# 1-Schematic_Smart_dual_relay_board.net
KiCad netlist of a schematic drawn in EasyEDA
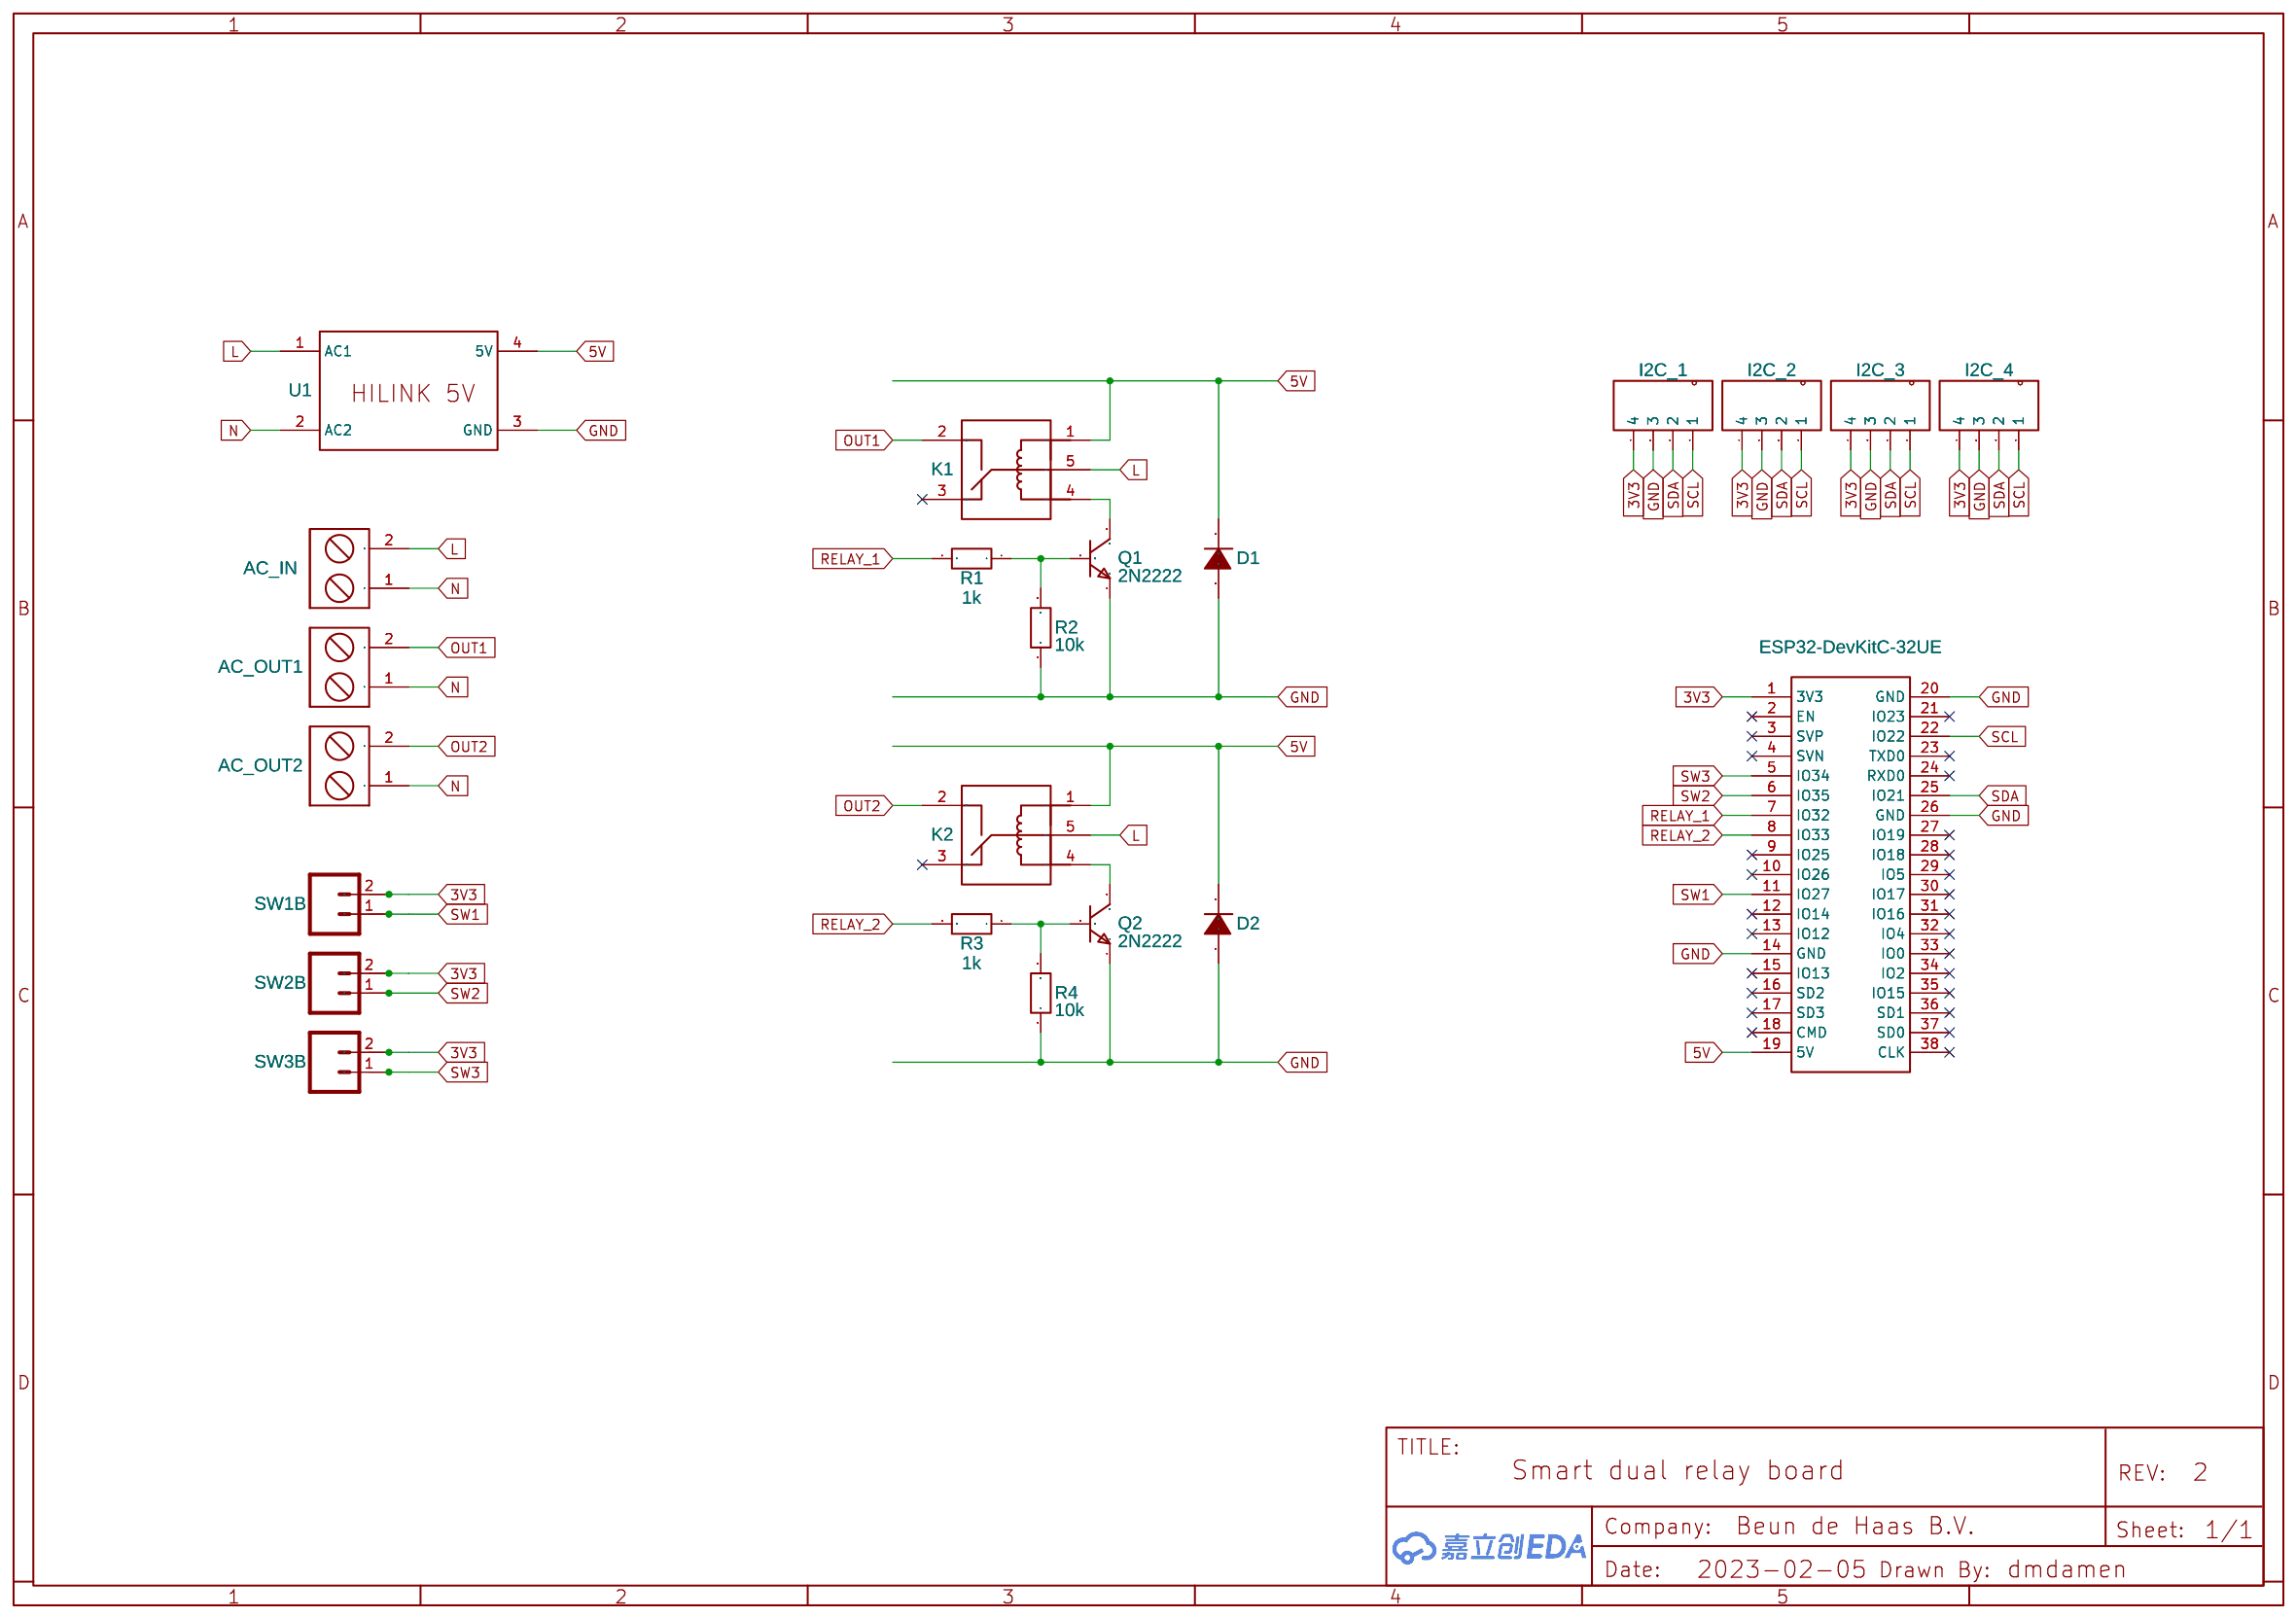
[diagram p0: schematic sheet]

(export (version "E")
  (design (tool "Eeschema 10.0.6"))
  (components
    (comp (ref "AC_IN")
      (value "10MM SCREW TERMINAL 2P")
      (libsource (lib "") (part "7.62MM PITCH 2 PIN BARRIER SCREW TERMINAL BLOCK CONNECTOR 300V 20A"))
    )
    (comp (ref "AC_OUT1")
      (value "10MM SCREW TERMINAL 2P")
      (libsource (lib "") (part "7.62MM PITCH 2 PIN BARRIER SCREW TERMINAL BLOCK CONNECTOR 300V 20A_1"))
    )
    (comp (ref "AC_OUT2")
      (value "10MM SCREW TERMINAL 2P")
      (libsource (lib "") (part "7.62MM PITCH 2 PIN BARRIER SCREW TERMINAL BLOCK CONNECTOR 300V 20A_1"))
    )
    (comp (ref "D1")
      (value "1N4001_C478800")
      (fields (field (name "BOM_Manufacturer Part") "1N4001") (field (name "BOM_Supplier Part") "C478800"))
      (libsource (lib "") (part "1N4001_C478800"))
    )
    (comp (ref "D2")
      (value "1N4001_C478800")
      (fields (field (name "BOM_Manufacturer Part") "1N4001") (field (name "BOM_Supplier Part") "C478800"))
      (libsource (lib "") (part "1N4001_C478800"))
    )
    (comp (ref "I2C_1") (value "I2C 1") (libsource (lib "") (part "PINHEADER-4PIN")))
    (comp (ref "I2C_2") (value "I2C 2") (libsource (lib "") (part "PINHEADER-4PIN")))
    (comp (ref "I2C_3") (value "I2C 3") (libsource (lib "") (part "PINHEADER-4PIN")))
    (comp (ref "I2C_4") (value "I2C 3") (libsource (lib "") (part "PINHEADER-4PIN")))
    (comp (ref "K1")
      (value "SRD-03VDC-SL-C_C496430")
      (fields
        (field (name "BOM_Manufacturer Part") "SRD-03VDC-SL-C")
        (field (name "BOM_Supplier Part") "C496430")
      )
      (libsource (lib "") (part "SRD-03VDC-SL-C_C496430"))
    )
    (comp (ref "K2")
      (value "SRD-03VDC-SL-C_C496430")
      (fields
        (field (name "BOM_Manufacturer Part") "SRD-03VDC-SL-C")
        (field (name "BOM_Supplier Part") "C496430")
      )
      (libsource (lib "") (part "SRD-03VDC-SL-C_C496430"))
    )
    (comp (ref "Q1")
      (value "2N2222")
      (fields (field (name "BOM_Manufacturer Part") "2N2222A") (field (name "BOM_Supplier Part") "C118536"))
      (libsource (lib "") (part "2N2222"))
    )
    (comp (ref "Q2")
      (value "2N2222")
      (fields (field (name "BOM_Manufacturer Part") "2N2222A") (field (name "BOM_Supplier Part") "C118536"))
      (libsource (lib "") (part "2N2222"))
    )
    (comp (ref "R1") (value "1k") (libsource (lib "") (part "R_0603_EU_1")))
    (comp (ref "R2") (value "10k") (libsource (lib "") (part "R_0603_EU")))
    (comp (ref "R3") (value "1k") (libsource (lib "") (part "R_0603_EU_1")))
    (comp (ref "R4") (value "10k") (libsource (lib "") (part "R_0603_EU")))
    (comp (ref "SW1B") (value "M02") (libsource (lib "") (part "M02")))
    (comp (ref "SW2B") (value "M02") (libsource (lib "") (part "M02_1")))
    (comp (ref "SW3B") (value "M02") (libsource (lib "") (part "M02_2")))
    (comp (ref "U1")
      (value "HILINK 5V corrected")
      (fields (field (name "BOM_Manufacturer Part") "HILINK 5V"))
      (libsource (lib "") (part "HILINK 5V corrected"))
    )
    (comp (ref "U2")
      (value "ESP32-DevKitC-32UE")
      (fields (field (name "BOM_Manufacturer Part") "ESP32 DEVKIT V.4"))
      (libsource (lib "") (part "ESP32-DevKitC-32UE"))
    )
  )
  (nets
    (net (code "1") (name "3V3") (class "Default")
      (node (ref "I2C_1") (pin "4") (pinfunction "4_4") (pintype "input"))
      (node (ref "I2C_2") (pin "4") (pinfunction "4_4") (pintype "input"))
      (node (ref "I2C_3") (pin "4") (pinfunction "4_4") (pintype "input"))
      (node (ref "I2C_4") (pin "4") (pinfunction "4_4") (pintype "input"))
      (node (ref "SW1B") (pin "2") (pinfunction "2_2") (pintype "unspecified"))
      (node (ref "SW2B") (pin "2") (pinfunction "2_2") (pintype "unspecified"))
      (node (ref "SW3B") (pin "2") (pinfunction "2_2") (pintype "unspecified"))
      (node (ref "U2") (pin "1") (pinfunction "3V3_1") (pintype "unspecified"))
    )
    (net (code "2") (name "5V") (class "Default")
      (node (ref "D1") (pin "1") (pinfunction "K_1") (pintype "unspecified"))
      (node (ref "D2") (pin "1") (pinfunction "K_1") (pintype "unspecified"))
      (node (ref "K1") (pin "1") (pinfunction "1_1") (pintype "unspecified"))
      (node (ref "K2") (pin "1") (pinfunction "1_1") (pintype "unspecified"))
      (node (ref "U1") (pin "4") (pinfunction "5V_4") (pintype "unspecified"))
      (node (ref "U2") (pin "19") (pinfunction "5V_19") (pintype "unspecified"))
    )
    (net (code "3") (name "GND") (class "Default")
      (node (ref "D1") (pin "2") (pinfunction "A_2") (pintype "unspecified"))
      (node (ref "D2") (pin "2") (pinfunction "A_2") (pintype "unspecified"))
      (node (ref "I2C_1") (pin "3") (pinfunction "3_3") (pintype "input"))
      (node (ref "I2C_2") (pin "3") (pinfunction "3_3") (pintype "input"))
      (node (ref "I2C_3") (pin "3") (pinfunction "3_3") (pintype "input"))
      (node (ref "I2C_4") (pin "3") (pinfunction "3_3") (pintype "input"))
      (node (ref "Q1") (pin "1") (pinfunction "E_1") (pintype "unspecified"))
      (node (ref "Q2") (pin "1") (pinfunction "E_1") (pintype "unspecified"))
      (node (ref "R2") (pin "1") (pinfunction "1_1") (pintype "unspecified"))
      (node (ref "R4") (pin "1") (pinfunction "1_1") (pintype "unspecified"))
      (node (ref "U1") (pin "3") (pinfunction "GND_3") (pintype "unspecified"))
      (node (ref "U2") (pin "14") (pinfunction "GND_14") (pintype "unspecified"))
      (node (ref "U2") (pin "20") (pinfunction "GND_20") (pintype "unspecified"))
      (node (ref "U2") (pin "26") (pinfunction "GND_26") (pintype "unspecified"))
    )
    (net (code "4") (name "L") (class "Default")
      (node (ref "AC_IN") (pin "2") (pinfunction "2_2") (pintype "unspecified"))
      (node (ref "K1") (pin "5") (pinfunction "5_5") (pintype "unspecified"))
      (node (ref "K2") (pin "5") (pinfunction "5_5") (pintype "unspecified"))
      (node (ref "U1") (pin "1") (pinfunction "AC1_1") (pintype "unspecified"))
    )
    (net (code "5") (name "N") (class "Default")
      (node (ref "AC_IN") (pin "1") (pinfunction "1_1") (pintype "unspecified"))
      (node (ref "AC_OUT1") (pin "1") (pinfunction "1_1") (pintype "unspecified"))
      (node (ref "AC_OUT2") (pin "1") (pinfunction "1_1") (pintype "unspecified"))
      (node (ref "U1") (pin "2") (pinfunction "AC2_2") (pintype "unspecified"))
    )
    (net (code "6") (name "Net-(Q1-B)") (class "Default")
      (node (ref "Q1") (pin "2") (pinfunction "B_2") (pintype "unspecified"))
      (node (ref "R1") (pin "1") (pinfunction "1_1") (pintype "unspecified"))
      (node (ref "R2") (pin "2") (pinfunction "2_2") (pintype "unspecified"))
    )
    (net (code "7") (name "Net-(Q1-C)") (class "Default")
      (node (ref "K1") (pin "4") (pinfunction "4_4") (pintype "unspecified"))
      (node (ref "Q1") (pin "3") (pinfunction "C_3") (pintype "unspecified"))
    )
    (net (code "8") (name "Net-(Q2-B)") (class "Default")
      (node (ref "Q2") (pin "2") (pinfunction "B_2") (pintype "unspecified"))
      (node (ref "R3") (pin "1") (pinfunction "1_1") (pintype "unspecified"))
      (node (ref "R4") (pin "2") (pinfunction "2_2") (pintype "unspecified"))
    )
    (net (code "9") (name "Net-(Q2-C)") (class "Default")
      (node (ref "K2") (pin "4") (pinfunction "4_4") (pintype "unspecified"))
      (node (ref "Q2") (pin "3") (pinfunction "C_3") (pintype "unspecified"))
    )
    (net (code "10") (name "OUT1") (class "Default")
      (node (ref "AC_OUT1") (pin "2") (pinfunction "2_2") (pintype "unspecified"))
      (node (ref "K1") (pin "2") (pinfunction "2_2") (pintype "unspecified"))
    )
    (net (code "11") (name "OUT2") (class "Default")
      (node (ref "AC_OUT2") (pin "2") (pinfunction "2_2") (pintype "unspecified"))
      (node (ref "K2") (pin "2") (pinfunction "2_2") (pintype "unspecified"))
    )
    (net (code "12") (name "RELAY_1") (class "Default")
      (node (ref "R1") (pin "2") (pinfunction "2_2") (pintype "unspecified"))
      (node (ref "U2") (pin "7") (pinfunction "IO32_7") (pintype "unspecified"))
    )
    (net (code "13") (name "RELAY_2") (class "Default")
      (node (ref "R3") (pin "2") (pinfunction "2_2") (pintype "unspecified"))
      (node (ref "U2") (pin "8") (pinfunction "IO33_8") (pintype "unspecified"))
    )
    (net (code "14") (name "SCL") (class "Default")
      (node (ref "I2C_1") (pin "1") (pinfunction "1_1") (pintype "input"))
      (node (ref "I2C_2") (pin "1") (pinfunction "1_1") (pintype "input"))
      (node (ref "I2C_3") (pin "1") (pinfunction "1_1") (pintype "input"))
      (node (ref "I2C_4") (pin "1") (pinfunction "1_1") (pintype "input"))
      (node (ref "U2") (pin "22") (pinfunction "IO22_22") (pintype "unspecified"))
    )
    (net (code "15") (name "SDA") (class "Default")
      (node (ref "I2C_1") (pin "2") (pinfunction "2_2") (pintype "input"))
      (node (ref "I2C_2") (pin "2") (pinfunction "2_2") (pintype "input"))
      (node (ref "I2C_3") (pin "2") (pinfunction "2_2") (pintype "input"))
      (node (ref "I2C_4") (pin "2") (pinfunction "2_2") (pintype "input"))
      (node (ref "U2") (pin "25") (pinfunction "IO21_25") (pintype "unspecified"))
    )
    (net (code "16") (name "SW1") (class "Default")
      (node (ref "SW1B") (pin "1") (pinfunction "1_1") (pintype "unspecified"))
      (node (ref "U2") (pin "11") (pinfunction "IO27_11") (pintype "unspecified"))
    )
    (net (code "17") (name "SW2") (class "Default")
      (node (ref "SW2B") (pin "1") (pinfunction "1_1") (pintype "unspecified"))
      (node (ref "U2") (pin "6") (pinfunction "IO35_6") (pintype "unspecified"))
    )
    (net (code "18") (name "SW3") (class "Default")
      (node (ref "SW3B") (pin "1") (pinfunction "1_1") (pintype "unspecified"))
      (node (ref "U2") (pin "5") (pinfunction "IO34_5") (pintype "unspecified"))
    )
    (net (code "19") (name "unconnected-(K1-Pad3)") (class "Default")
      (node (ref "K1") (pin "3") (pinfunction "3_3") (pintype "unspecified+no_connect"))
    )
    (net (code "20") (name "unconnected-(K2-Pad3)") (class "Default")
      (node (ref "K2") (pin "3") (pinfunction "3_3") (pintype "unspecified+no_connect"))
    )
    (net (code "21") (name "unconnected-(U2-CLK-Pad38)") (class "Default")
      (node (ref "U2") (pin "38") (pinfunction "CLK_38") (pintype "unspecified+no_connect"))
    )
    (net (code "22") (name "unconnected-(U2-CMD-Pad18)") (class "Default")
      (node (ref "U2") (pin "18") (pinfunction "CMD_18") (pintype "unspecified+no_connect"))
    )
    (net (code "23") (name "unconnected-(U2-EN-Pad2)") (class "Default")
      (node (ref "U2") (pin "2") (pinfunction "EN_2") (pintype "unspecified+no_connect"))
    )
    (net (code "24") (name "unconnected-(U2-IO0-Pad33)") (class "Default")
      (node (ref "U2") (pin "33") (pinfunction "IO0_33") (pintype "unspecified+no_connect"))
    )
    (net (code "25") (name "unconnected-(U2-IO2-Pad34)") (class "Default")
      (node (ref "U2") (pin "34") (pinfunction "IO2_34") (pintype "unspecified+no_connect"))
    )
    (net (code "26") (name "unconnected-(U2-IO4-Pad32)") (class "Default")
      (node (ref "U2") (pin "32") (pinfunction "IO4_32") (pintype "unspecified+no_connect"))
    )
    (net (code "27") (name "unconnected-(U2-IO5-Pad29)") (class "Default")
      (node (ref "U2") (pin "29") (pinfunction "IO5_29") (pintype "unspecified+no_connect"))
    )
    (net (code "28") (name "unconnected-(U2-IO12-Pad13)") (class "Default")
      (node (ref "U2") (pin "13") (pinfunction "IO12_13") (pintype "unspecified+no_connect"))
    )
    (net (code "29") (name "unconnected-(U2-IO13-Pad15)") (class "Default")
      (node (ref "U2") (pin "15") (pinfunction "IO13_15") (pintype "unspecified+no_connect"))
    )
    (net (code "30") (name "unconnected-(U2-IO14-Pad12)") (class "Default")
      (node (ref "U2") (pin "12") (pinfunction "IO14_12") (pintype "unspecified+no_connect"))
    )
    (net (code "31") (name "unconnected-(U2-IO15-Pad35)") (class "Default")
      (node (ref "U2") (pin "35") (pinfunction "IO15_35") (pintype "unspecified+no_connect"))
    )
    (net (code "32") (name "unconnected-(U2-IO16-Pad31)") (class "Default")
      (node (ref "U2") (pin "31") (pinfunction "IO16_31") (pintype "unspecified+no_connect"))
    )
    (net (code "33") (name "unconnected-(U2-IO17-Pad30)") (class "Default")
      (node (ref "U2") (pin "30") (pinfunction "IO17_30") (pintype "unspecified+no_connect"))
    )
    (net (code "34") (name "unconnected-(U2-IO18-Pad28)") (class "Default")
      (node (ref "U2") (pin "28") (pinfunction "IO18_28") (pintype "unspecified+no_connect"))
    )
    (net (code "35") (name "unconnected-(U2-IO19-Pad27)") (class "Default")
      (node (ref "U2") (pin "27") (pinfunction "IO19_27") (pintype "unspecified+no_connect"))
    )
    (net (code "36") (name "unconnected-(U2-IO23-Pad21)") (class "Default")
      (node (ref "U2") (pin "21") (pinfunction "IO23_21") (pintype "unspecified+no_connect"))
    )
    (net (code "37") (name "unconnected-(U2-IO25-Pad9)") (class "Default")
      (node (ref "U2") (pin "9") (pinfunction "IO25_9") (pintype "unspecified+no_connect"))
    )
    (net (code "38") (name "unconnected-(U2-IO26-Pad10)") (class "Default")
      (node (ref "U2") (pin "10") (pinfunction "IO26_10") (pintype "unspecified+no_connect"))
    )
    (net (code "39") (name "unconnected-(U2-RXD0-Pad24)") (class "Default")
      (node (ref "U2") (pin "24") (pinfunction "RXD0_24") (pintype "unspecified+no_connect"))
    )
    (net (code "40") (name "unconnected-(U2-SD0-Pad37)") (class "Default")
      (node (ref "U2") (pin "37") (pinfunction "SD0_37") (pintype "unspecified+no_connect"))
    )
    (net (code "41") (name "unconnected-(U2-SD1-Pad36)") (class "Default")
      (node (ref "U2") (pin "36") (pinfunction "SD1_36") (pintype "unspecified+no_connect"))
    )
    (net (code "42") (name "unconnected-(U2-SD2-Pad16)") (class "Default")
      (node (ref "U2") (pin "16") (pinfunction "SD2_16") (pintype "unspecified+no_connect"))
    )
    (net (code "43") (name "unconnected-(U2-SD3-Pad17)") (class "Default")
      (node (ref "U2") (pin "17") (pinfunction "SD3_17") (pintype "unspecified+no_connect"))
    )
    (net (code "44") (name "unconnected-(U2-SVN-Pad4)") (class "Default")
      (node (ref "U2") (pin "4") (pinfunction "SVN_4") (pintype "unspecified+no_connect"))
    )
    (net (code "45") (name "unconnected-(U2-SVP-Pad3)") (class "Default")
      (node (ref "U2") (pin "3") (pinfunction "SVP_3") (pintype "unspecified+no_connect"))
    )
    (net (code "46") (name "unconnected-(U2-TXD0-Pad23)") (class "Default")
      (node (ref "U2") (pin "23") (pinfunction "TXD0_23") (pintype "unspecified+no_connect"))
    )
  )
)
